# DeadHorsePCB_REV-B_Shrink.net
KiCad netlist of a schematic drawn in EAGLE
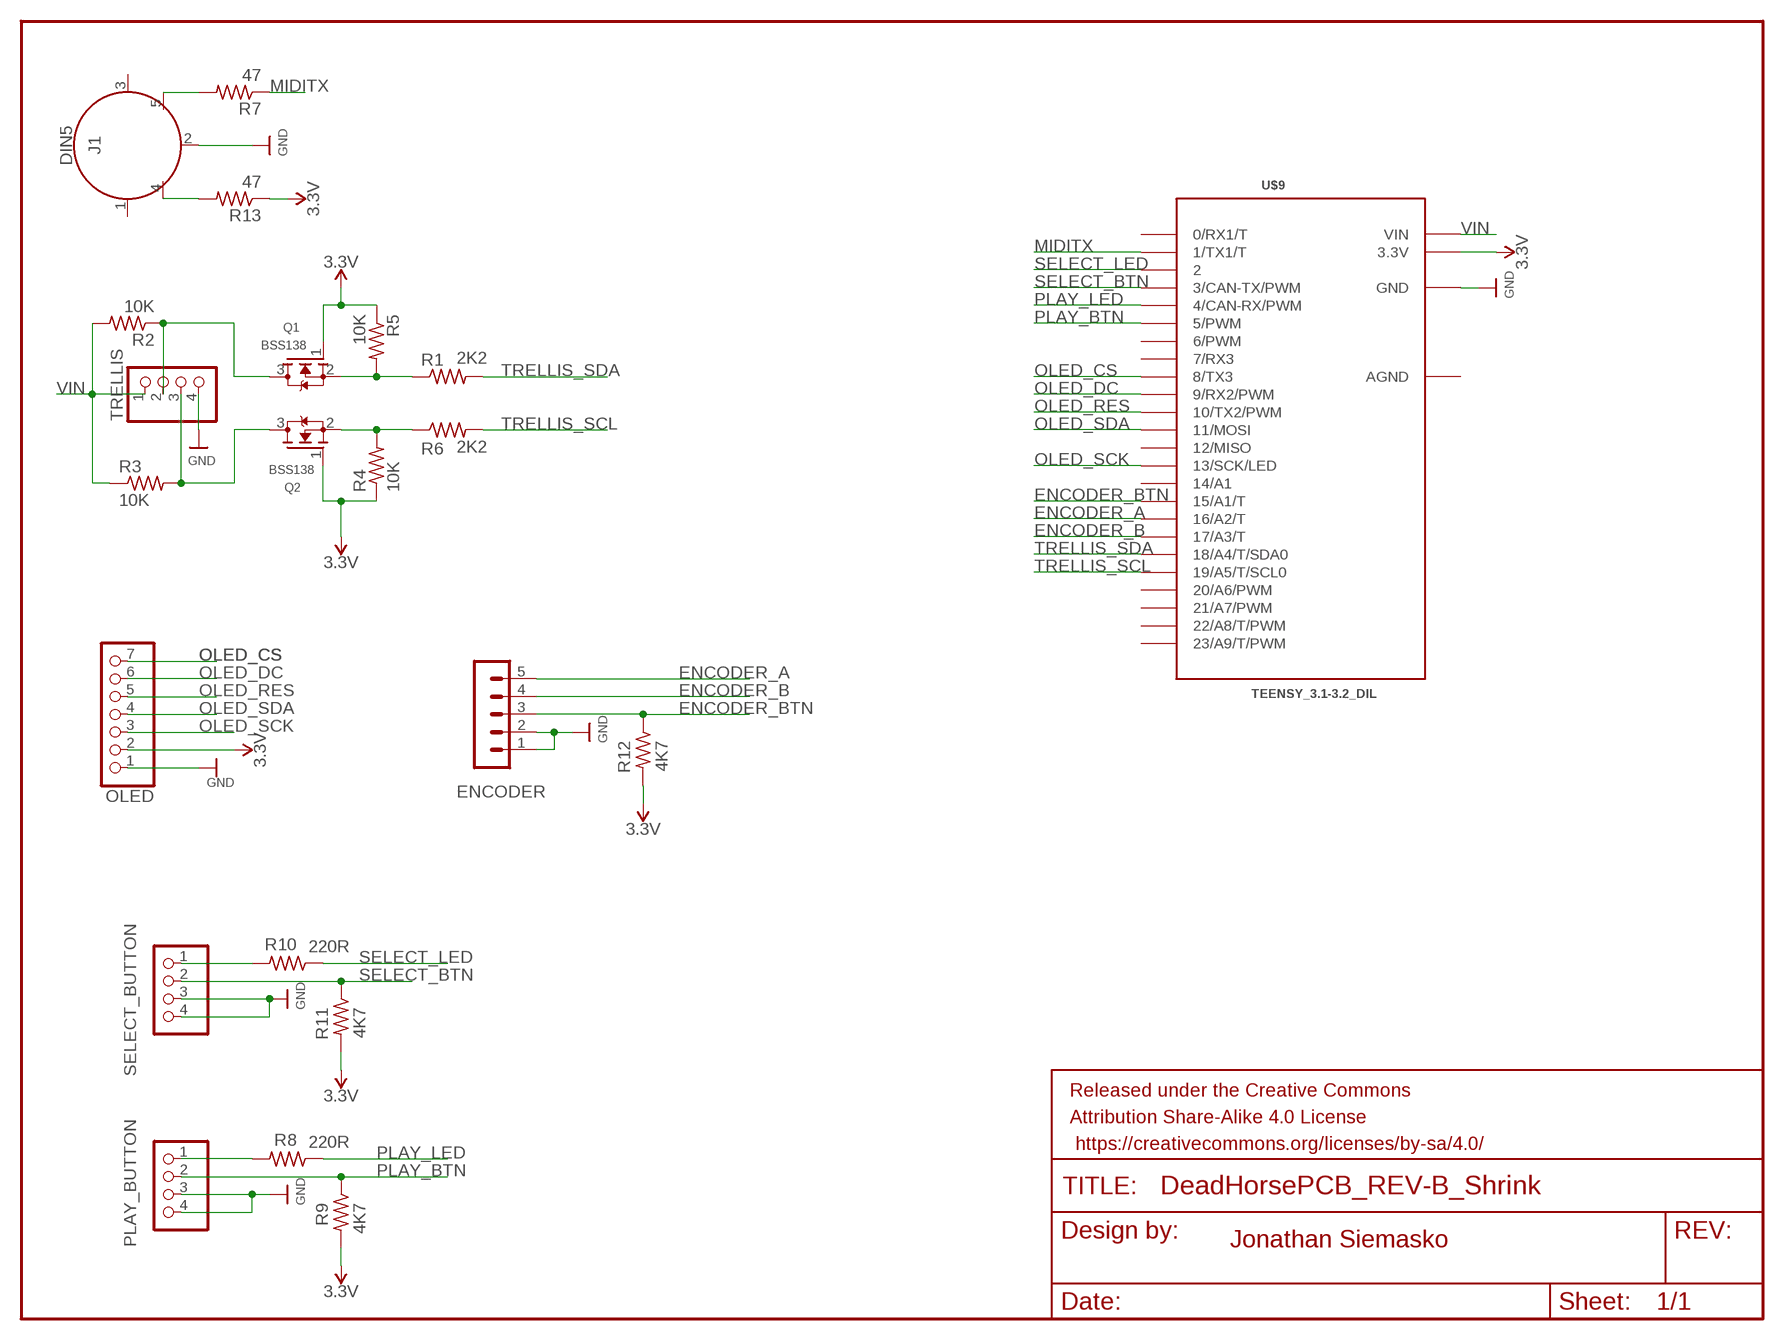
[diagram p0: schematic, sheet 1]

(export (version "E")
  (design (tool "Eeschema 10.0.6"))
  (components
    (comp (ref "ENCODER")
      (value "ENCODER")
      (footprint "eagle-import:MA05-1")
      (libsource (lib "eagle-import") (part "MA05-1"))
    )
    (comp (ref "FRAME1")
      (value "FRAME-LETTER")
      (footprint "eagle-import:CREATIVE_COMMONS")
      (libsource (lib "eagle-import") (part "FRAME-LETTER"))
    )
    (comp (ref "J1")
      (value "DIN5")
      (footprint "eagle-import:DIN5-RA-PTH")
      (libsource (lib "eagle-import") (part "DIN5"))
    )
    (comp (ref "OLED")
      (value "OLED")
      (footprint "eagle-import:1X07")
      (libsource (lib "eagle-import") (part "PINHD-1X7"))
    )
    (comp (ref "PLAY_BUTTON")
      (value "PlayBtn")
      (footprint "eagle-import:1X04")
      (libsource (lib "eagle-import") (part "PINHD-1X4"))
    )
    (comp (ref "Q1")
      (value "BSS138")
      (footprint "eagle-import:SOT23")
      (libsource (lib "eagle-import") (part "MOSFET-NREFLOW"))
    )
    (comp (ref "Q2")
      (value "BSS138")
      (footprint "eagle-import:SOT23")
      (libsource (lib "eagle-import") (part "MOSFET-NREFLOW"))
    )
    (comp (ref "R1")
      (value "2K2")
      (footprint "eagle-import:R0805")
      (libsource (lib "eagle-import") (part "R-US_R0805"))
    )
    (comp (ref "R2")
      (value "10K")
      (footprint "eagle-import:R0805")
      (libsource (lib "eagle-import") (part "R-US_R0805"))
    )
    (comp (ref "R3")
      (value "10K")
      (footprint "eagle-import:R0805")
      (libsource (lib "eagle-import") (part "R-US_R0805"))
    )
    (comp (ref "R4")
      (value "10K")
      (footprint "eagle-import:R0805")
      (libsource (lib "eagle-import") (part "R-US_R0805"))
    )
    (comp (ref "R5")
      (value "10K")
      (footprint "eagle-import:R0805")
      (libsource (lib "eagle-import") (part "R-US_R0805"))
    )
    (comp (ref "R6")
      (value "2K2")
      (footprint "eagle-import:R0805")
      (libsource (lib "eagle-import") (part "R-US_R0805"))
    )
    (comp (ref "R7")
      (value "47")
      (footprint "eagle-import:R0805")
      (libsource (lib "eagle-import") (part "R-US_R0805"))
    )
    (comp (ref "R8")
      (value "220R")
      (footprint "eagle-import:R0805")
      (libsource (lib "eagle-import") (part "R-US_R0805"))
    )
    (comp (ref "R9")
      (value "4K7")
      (footprint "eagle-import:R0805")
      (libsource (lib "eagle-import") (part "R-US_R0805"))
    )
    (comp (ref "R10")
      (value "220R")
      (footprint "eagle-import:R0805")
      (libsource (lib "eagle-import") (part "R-US_R0805"))
    )
    (comp (ref "R11")
      (value "4K7")
      (footprint "eagle-import:R0805")
      (libsource (lib "eagle-import") (part "R-US_R0805"))
    )
    (comp (ref "R12")
      (value "4K7")
      (footprint "eagle-import:R0805")
      (libsource (lib "eagle-import") (part "R-US_R0805"))
    )
    (comp (ref "R13")
      (value "47")
      (footprint "eagle-import:R0805")
      (libsource (lib "eagle-import") (part "R-US_R0805"))
    )
    (comp (ref "SELECT_BUTTON")
      (value "SelectBtn")
      (footprint "eagle-import:1X04")
      (libsource (lib "eagle-import") (part "PINHD-1X4"))
    )
    (comp (ref "TRELLIS")
      (value "TRELLIS")
      (footprint "eagle-import:1X04")
      (libsource (lib "eagle-import") (part "PINHD-1X4"))
    )
    (comp (ref "U$9")
      (value "TEENSY_3.1-3.2_DIL")
      (footprint "eagle-import:TEENSY_3.0-3.2&LC_DIL")
      (libsource (lib "eagle-import") (part "TEENSY_3.1-3.2_DIL"))
    )
  )
  (nets
    (net (code "1") (name "/AGND") (class "Default")
      (node (ref "U$9") (pin "AGND") (pinfunction "AGND_AGND") (pintype "power_in"))
    )
    (net (code "2") (name "/ENCODER_A") (class "Default")
      (node (ref "ENCODER") (pin "5") (pinfunction "5_5") (pintype "passive"))
      (node (ref "U$9") (pin "16/A2") (pinfunction "16/A2/T_16/A2") (pintype "bidirectional"))
    )
    (net (code "3") (name "/ENCODER_B") (class "Default")
      (node (ref "ENCODER") (pin "4") (pinfunction "4_4") (pintype "passive"))
      (node (ref "U$9") (pin "17/A3") (pinfunction "17/A3/T_17/A3") (pintype "bidirectional"))
    )
    (net (code "4") (name "/ENCODER_BTN") (class "Default")
      (node (ref "ENCODER") (pin "3") (pinfunction "3_3") (pintype "passive"))
      (node (ref "R12") (pin "1") (pinfunction "1_1") (pintype "passive"))
      (node (ref "U$9") (pin "15/A1") (pinfunction "15/A1/T_15/A1") (pintype "bidirectional"))
    )
    (net (code "5") (name "/MIDITX") (class "Default")
      (node (ref "R7") (pin "1") (pinfunction "1_1") (pintype "passive"))
      (node (ref "U$9") (pin "1") (pinfunction "1/TX1/T_1") (pintype "bidirectional"))
    )
    (net (code "6") (name "/OLED_CS") (class "Default")
      (node (ref "OLED") (pin "7") (pinfunction "7_7") (pintype "passive"))
      (node (ref "U$9") (pin "8") (pinfunction "8/TX3_8") (pintype "bidirectional"))
    )
    (net (code "7") (name "/OLED_DC") (class "Default")
      (node (ref "OLED") (pin "6") (pinfunction "6_6") (pintype "passive"))
      (node (ref "U$9") (pin "9") (pinfunction "9/RX2/PWM_9") (pintype "bidirectional"))
    )
    (net (code "8") (name "/OLED_RES") (class "Default")
      (node (ref "OLED") (pin "5") (pinfunction "5_5") (pintype "passive"))
      (node (ref "U$9") (pin "10") (pinfunction "10/TX2/PWM_10") (pintype "bidirectional"))
    )
    (net (code "9") (name "/OLED_SCK") (class "Default")
      (node (ref "OLED") (pin "3") (pinfunction "3_3") (pintype "passive"))
      (node (ref "U$9") (pin "13") (pinfunction "13/SCK/LED_13") (pintype "bidirectional"))
    )
    (net (code "10") (name "/OLED_SDA") (class "Default")
      (node (ref "OLED") (pin "4") (pinfunction "4_4") (pintype "passive"))
      (node (ref "U$9") (pin "11") (pinfunction "11/MOSI_11") (pintype "bidirectional"))
    )
    (net (code "11") (name "/PLAY_BTN") (class "Default")
      (node (ref "PLAY_BUTTON") (pin "2") (pinfunction "2_2") (pintype "passive"))
      (node (ref "R9") (pin "1") (pinfunction "1_1") (pintype "passive"))
      (node (ref "U$9") (pin "5") (pinfunction "5/PWM_5") (pintype "bidirectional"))
    )
    (net (code "12") (name "/PLAY_LED") (class "Default")
      (node (ref "R8") (pin "1") (pinfunction "1_1") (pintype "passive"))
      (node (ref "U$9") (pin "4") (pinfunction "4/CAN-RX/PWM_4") (pintype "bidirectional"))
    )
    (net (code "13") (name "/SELECT_BTN") (class "Default")
      (node (ref "R11") (pin "1") (pinfunction "1_1") (pintype "passive"))
      (node (ref "SELECT_BUTTON") (pin "2") (pinfunction "2_2") (pintype "passive"))
      (node (ref "U$9") (pin "3") (pinfunction "3/CAN-TX/PWM_3") (pintype "bidirectional"))
    )
    (net (code "14") (name "/SELECT_LED") (class "Default")
      (node (ref "R10") (pin "1") (pinfunction "1_1") (pintype "passive"))
      (node (ref "U$9") (pin "2") (pinfunction "2_2") (pintype "bidirectional"))
    )
    (net (code "15") (name "/TRELLIS_SCL") (class "Default")
      (node (ref "R6") (pin "2") (pinfunction "2_2") (pintype "passive"))
      (node (ref "U$9") (pin "19/A5") (pinfunction "19/A5/T/SCL0_19/A5") (pintype "bidirectional"))
    )
    (net (code "16") (name "/TRELLIS_SDA") (class "Default")
      (node (ref "R1") (pin "2") (pinfunction "2_2") (pintype "passive"))
      (node (ref "U$9") (pin "18/A4") (pinfunction "18/A4/T/SDA0_18/A4") (pintype "bidirectional"))
    )
    (net (code "17") (name "/VIN") (class "Default")
      (node (ref "R2") (pin "2") (pinfunction "2_2") (pintype "passive"))
      (node (ref "R3") (pin "1") (pinfunction "1_1") (pintype "passive"))
      (node (ref "TRELLIS") (pin "1") (pinfunction "1_1") (pintype "passive"))
      (node (ref "U$9") (pin "VIN") (pinfunction "VIN_VIN") (pintype "power_in"))
    )
    (net (code "18") (name "3.3V") (class "Default")
      (node (ref "OLED") (pin "2") (pinfunction "2_2") (pintype "passive"))
      (node (ref "Q1") (pin "1") (pinfunction "G_1") (pintype "bidirectional"))
      (node (ref "Q2") (pin "1") (pinfunction "G_1") (pintype "bidirectional"))
      (node (ref "R11") (pin "2") (pinfunction "2_2") (pintype "passive"))
      (node (ref "R12") (pin "2") (pinfunction "2_2") (pintype "passive"))
      (node (ref "R13") (pin "1") (pinfunction "1_1") (pintype "passive"))
      (node (ref "R4") (pin "1") (pinfunction "1_1") (pintype "passive"))
      (node (ref "R5") (pin "1") (pinfunction "1_1") (pintype "passive"))
      (node (ref "R9") (pin "2") (pinfunction "2_2") (pintype "passive"))
      (node (ref "U$9") (pin "3.3V") (pinfunction "3.3V_3.3V") (pintype "power_in"))
    )
    (net (code "19") (name "GND") (class "Default")
      (node (ref "ENCODER") (pin "1") (pinfunction "1_1") (pintype "passive"))
      (node (ref "ENCODER") (pin "2") (pinfunction "2_2") (pintype "passive"))
      (node (ref "J1") (pin "2") (pinfunction "2_2") (pintype "bidirectional"))
      (node (ref "OLED") (pin "1") (pinfunction "1_1") (pintype "passive"))
      (node (ref "PLAY_BUTTON") (pin "3") (pinfunction "3_3") (pintype "passive"))
      (node (ref "PLAY_BUTTON") (pin "4") (pinfunction "4_4") (pintype "passive"))
      (node (ref "SELECT_BUTTON") (pin "3") (pinfunction "3_3") (pintype "passive"))
      (node (ref "SELECT_BUTTON") (pin "4") (pinfunction "4_4") (pintype "passive"))
      (node (ref "TRELLIS") (pin "4") (pinfunction "4_4") (pintype "passive"))
      (node (ref "U$9") (pin "GND") (pinfunction "GND_GND") (pintype "power_in"))
    )
    (net (code "20") (name "Net-(J1-Pad4)") (class "Default")
      (node (ref "J1") (pin "4") (pinfunction "4_4") (pintype "bidirectional"))
      (node (ref "R13") (pin "2") (pinfunction "2_2") (pintype "passive"))
    )
    (net (code "21") (name "Net-(J1-Pad5)") (class "Default")
      (node (ref "J1") (pin "5") (pinfunction "5_5") (pintype "bidirectional"))
      (node (ref "R7") (pin "2") (pinfunction "2_2") (pintype "passive"))
    )
    (net (code "22") (name "Net-(PLAY_BUTTON-Pad1)") (class "Default")
      (node (ref "PLAY_BUTTON") (pin "1") (pinfunction "1_1") (pintype "passive"))
      (node (ref "R8") (pin "2") (pinfunction "2_2") (pintype "passive"))
    )
    (net (code "23") (name "Net-(Q1-D)") (class "Default")
      (node (ref "Q1") (pin "3") (pinfunction "D_3") (pintype "bidirectional"))
      (node (ref "R2") (pin "1") (pinfunction "1_1") (pintype "passive"))
      (node (ref "TRELLIS") (pin "2") (pinfunction "2_2") (pintype "passive"))
    )
    (net (code "24") (name "Net-(Q1-S)") (class "Default")
      (node (ref "Q1") (pin "2") (pinfunction "S_2") (pintype "bidirectional"))
      (node (ref "R1") (pin "1") (pinfunction "1_1") (pintype "passive"))
      (node (ref "R5") (pin "2") (pinfunction "2_2") (pintype "passive"))
    )
    (net (code "25") (name "Net-(Q2-D)") (class "Default")
      (node (ref "Q2") (pin "3") (pinfunction "D_3") (pintype "bidirectional"))
      (node (ref "R3") (pin "2") (pinfunction "2_2") (pintype "passive"))
      (node (ref "TRELLIS") (pin "3") (pinfunction "3_3") (pintype "passive"))
    )
    (net (code "26") (name "Net-(Q2-S)") (class "Default")
      (node (ref "Q2") (pin "2") (pinfunction "S_2") (pintype "bidirectional"))
      (node (ref "R4") (pin "2") (pinfunction "2_2") (pintype "passive"))
      (node (ref "R6") (pin "1") (pinfunction "1_1") (pintype "passive"))
    )
    (net (code "27") (name "Net-(R10-Pad2)") (class "Default")
      (node (ref "R10") (pin "2") (pinfunction "2_2") (pintype "passive"))
      (node (ref "SELECT_BUTTON") (pin "1") (pinfunction "1_1") (pintype "passive"))
    )
    (net (code "28") (name "unconnected-(J1-Pad1)") (class "Default")
      (node (ref "J1") (pin "1") (pinfunction "1_1") (pintype "bidirectional"))
    )
    (net (code "29") (name "unconnected-(J1-Pad3)") (class "Default")
      (node (ref "J1") (pin "3") (pinfunction "3_3") (pintype "bidirectional"))
    )
    (net (code "30") (name "unconnected-(U$9-0{slash}RX1{slash}T-Pad0)") (class "Default")
      (node (ref "U$9") (pin "0") (pinfunction "0/RX1/T_0") (pintype "bidirectional"))
    )
    (net (code "31") (name "unconnected-(U$9-6{slash}PWM-Pad6)") (class "Default")
      (node (ref "U$9") (pin "6") (pinfunction "6/PWM_6") (pintype "bidirectional"))
    )
    (net (code "32") (name "unconnected-(U$9-7{slash}RX3-Pad7)") (class "Default")
      (node (ref "U$9") (pin "7") (pinfunction "7/RX3_7") (pintype "bidirectional"))
    )
    (net (code "33") (name "unconnected-(U$9-12{slash}MISO-Pad12)") (class "Default")
      (node (ref "U$9") (pin "12") (pinfunction "12/MISO_12") (pintype "bidirectional"))
    )
    (net (code "34") (name "unconnected-(U$9-14{slash}A1-Pad14{slash}A0)") (class "Default")
      (node (ref "U$9") (pin "14/A0") (pinfunction "14/A1_14/A0") (pintype "bidirectional"))
    )
    (net (code "35") (name "unconnected-(U$9-20{slash}A6{slash}PWM-Pad20{slash}A6)") (class "Default")
      (node (ref "U$9") (pin "20/A6") (pinfunction "20/A6/PWM_20/A6") (pintype "bidirectional"))
    )
    (net (code "36") (name "unconnected-(U$9-21{slash}A7{slash}PWM-Pad21{slash}A7)") (class "Default")
      (node (ref "U$9") (pin "21/A7") (pinfunction "21/A7/PWM_21/A7") (pintype "bidirectional"))
    )
    (net (code "37") (name "unconnected-(U$9-22{slash}A8{slash}T{slash}PWM-Pad22{slash}A8)") (class "Default")
      (node (ref "U$9") (pin "22/A8") (pinfunction "22/A8/T/PWM_22/A8") (pintype "bidirectional"))
    )
    (net (code "38") (name "unconnected-(U$9-23{slash}A9{slash}T{slash}PWM-Pad23{slash}A9)") (class "Default")
      (node (ref "U$9") (pin "23/A9") (pinfunction "23/A9/T/PWM_23/A9") (pintype "bidirectional"))
    )
  )
)
